# Mosquito2.net
KiCad netlist of a schematic drawn in EAGLE
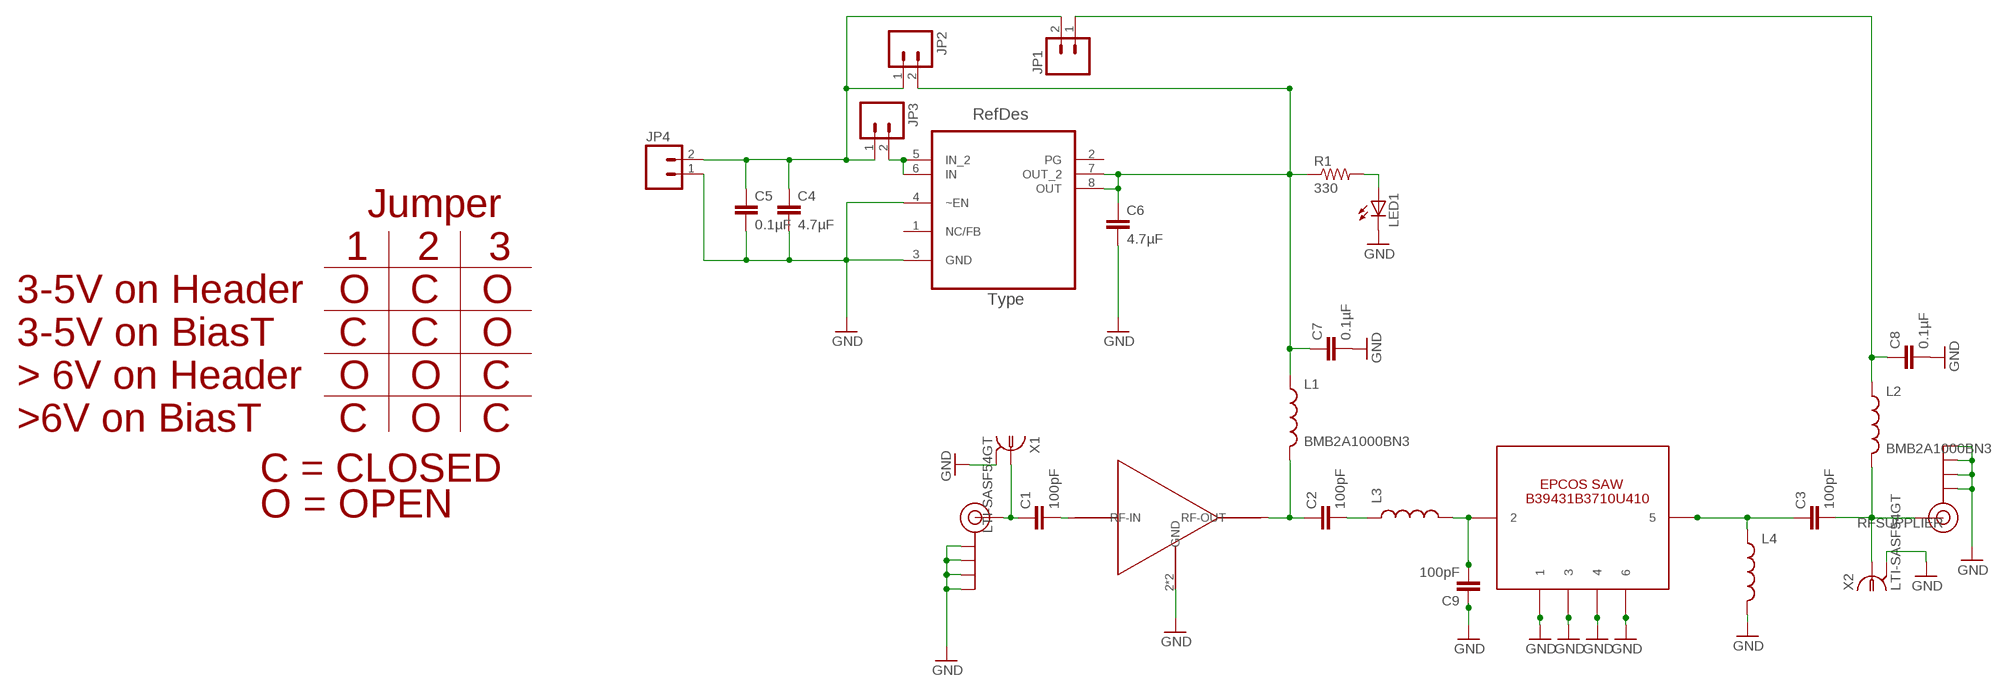
[diagram p0: schematic, sheet 1]

(export (version "E")
  (design (tool "Eeschema 10.0.6"))
  (components
    (comp (ref "C1")
      (value "100pF")
      (footprint "eagle-import:0603-CAP")
      (libsource (lib "eagle-import") (part "CAP0603-CAP"))
    )
    (comp (ref "C2")
      (value "100pF")
      (footprint "eagle-import:0603-CAP")
      (libsource (lib "eagle-import") (part "CAP0603-CAP"))
    )
    (comp (ref "C3")
      (value "100pF")
      (footprint "eagle-import:0603-CAP")
      (libsource (lib "eagle-import") (part "CAP0603-CAP"))
    )
    (comp (ref "C4")
      (value "4.7µF")
      (footprint "eagle-import:0805")
      (libsource (lib "eagle-import") (part "CAP0805"))
    )
    (comp (ref "C5")
      (value "0.1µF")
      (footprint "eagle-import:0603-CAP")
      (libsource (lib "eagle-import") (part "CAP0603-CAP"))
    )
    (comp (ref "C6")
      (value "4.7µF")
      (footprint "eagle-import:0805")
      (libsource (lib "eagle-import") (part "CAP0805"))
    )
    (comp (ref "C7")
      (value "0.1µF")
      (footprint "eagle-import:0603-CAP")
      (libsource (lib "eagle-import") (part "CAP0603-CAP"))
    )
    (comp (ref "C8")
      (value "0.1µF")
      (footprint "eagle-import:0603-CAP")
      (libsource (lib "eagle-import") (part "CAP0603-CAP"))
    )
    (comp (ref "C9")
      (value "100pF")
      (footprint "eagle-import:0603-CAP")
      (libsource (lib "eagle-import") (part "CAP0603-CAP"))
    )
    (comp (ref "IN")
      (value "SMA_EDGE")
      (footprint "eagle-import:SMA-EDGE")
      (libsource (lib "eagle-import") (part "SMA_EDGE"))
    )
    (comp (ref "JP1")
      (value "M02PTH")
      (footprint "eagle-import:1X02")
      (libsource (lib "eagle-import") (part "M02PTH"))
    )
    (comp (ref "JP2")
      (value "M02PTH")
      (footprint "eagle-import:1X02")
      (libsource (lib "eagle-import") (part "M02PTH"))
    )
    (comp (ref "JP3")
      (value "M02PTH")
      (footprint "eagle-import:1X02")
      (libsource (lib "eagle-import") (part "M02PTH"))
    )
    (comp (ref "JP4")
      (value "M02PTH")
      (footprint "eagle-import:1X02")
      (libsource (lib "eagle-import") (part "M02PTH"))
    )
    (comp (ref "L1")
      (value "BMB2A1000BN3")
      (footprint "eagle-import:0805")
      (libsource (lib "eagle-import") (part "INDUCTOR0805"))
    )
    (comp (ref "L2")
      (value "BMB2A1000BN3")
      (footprint "eagle-import:0805")
      (libsource (lib "eagle-import") (part "INDUCTOR0805"))
    )
    (comp (ref "L3")
      (value "INDUCTOR0603")
      (footprint "eagle-import:0603")
      (libsource (lib "eagle-import") (part "SparkFun-Passives_INDUCTOR0603"))
    )
    (comp (ref "L4")
      (value "INDUCTOR0603")
      (footprint "eagle-import:0603")
      (libsource (lib "eagle-import") (part "SparkFun-Passives_INDUCTOR0603"))
    )
    (comp (ref "LED1")
      (value "LEDCHIP-LED0603")
      (footprint "eagle-import:CHIP-LED0603")
      (libsource (lib "eagle-import") (part "LEDCHIP-LED0603"))
    )
    (comp (ref "OUT")
      (value "SMA_EDGE")
      (footprint "eagle-import:SMA-EDGE")
      (libsource (lib "eagle-import") (part "SMA_EDGE"))
    )
    (comp (ref "R1")
      (value "330")
      (footprint "eagle-import:0402-RES")
      (libsource (lib "eagle-import") (part "RESISTOR0402-RES"))
    )
    (comp (ref "U$1")
      (value "AVA_EPCOS_SAW_FILTER")
      (footprint "eagle-import:AVA_EPCOS_SAW_FILTER")
      (libsource (lib "eagle-import") (part "AVA_EPCOS_SAW_FILTER"))
    )
    (comp (ref "U$2")
      (value "PSA4-5043+")
      (footprint "eagle-import:PSA4-5043+")
      (libsource (lib "eagle-import") (part "PSA4-5043+"))
    )
    (comp (ref "U1")
      (value "TPS76633D")
      (footprint "eagle-import:SOIC127P600X175-8N")
      (libsource (lib "eagle-import") (part "TPS76633D"))
    )
    (comp (ref "X1")
      (value "LTI-SASF54GT")
      (footprint "eagle-import:LTI-SASF54GT")
      (libsource (lib "eagle-import") (part "LTI-SASF54GT"))
    )
    (comp (ref "X2")
      (value "LTI-SASF54GT")
      (footprint "eagle-import:LTI-SASF54GT")
      (libsource (lib "eagle-import") (part "LTI-SASF54GT"))
    )
  )
  (nets
    (net (code "1") (name "GND") (class "Default")
      (node (ref "C4") (pin "2") (pinfunction "2_2") (pintype "passive"))
      (node (ref "C5") (pin "2") (pinfunction "2_2") (pintype "passive"))
      (node (ref "C6") (pin "2") (pinfunction "2_2") (pintype "passive"))
      (node (ref "C7") (pin "2") (pinfunction "2_2") (pintype "passive"))
      (node (ref "C8") (pin "2") (pinfunction "2_2") (pintype "passive"))
      (node (ref "C9") (pin "1") (pinfunction "1_1") (pintype "passive"))
      (node (ref "IN") (pin "GND@0") (pinfunction "GND_GND@0") (pintype "bidirectional"))
      (node (ref "IN") (pin "GND@1") (pinfunction "GND_GND@1") (pintype "bidirectional"))
      (node (ref "IN") (pin "GND@2") (pinfunction "GND_GND@2") (pintype "bidirectional"))
      (node (ref "IN") (pin "GND@3") (pinfunction "GND_GND@3") (pintype "bidirectional"))
      (node (ref "JP4") (pin "1") (pinfunction "1_1") (pintype "passive"))
      (node (ref "L4") (pin "2") (pinfunction "2_2") (pintype "passive"))
      (node (ref "LED1") (pin "C") (pinfunction "C_C") (pintype "passive"))
      (node (ref "OUT") (pin "GND@0") (pinfunction "GND_GND@0") (pintype "bidirectional"))
      (node (ref "OUT") (pin "GND@1") (pinfunction "GND_GND@1") (pintype "bidirectional"))
      (node (ref "OUT") (pin "GND@2") (pinfunction "GND_GND@2") (pintype "bidirectional"))
      (node (ref "OUT") (pin "GND@3") (pinfunction "GND_GND@3") (pintype "bidirectional"))
      (node (ref "U$1") (pin "P$1") (pinfunction "1_P$1") (pintype "bidirectional"))
      (node (ref "U$1") (pin "P$3") (pinfunction "3_P$3") (pintype "bidirectional"))
      (node (ref "U$1") (pin "P$4") (pinfunction "4_P$4") (pintype "bidirectional"))
      (node (ref "U$1") (pin "P$6") (pinfunction "6_P$6") (pintype "bidirectional"))
      (node (ref "U$2") (pin "2") (pinfunction "GND_2") (pintype "bidirectional"))
      (node (ref "U$2") (pin "4") (pinfunction "GND_4") (pintype "bidirectional"))
      (node (ref "U1") (pin "3") (pinfunction "GND_3") (pintype "passive"))
      (node (ref "U1") (pin "4") (pinfunction "~{EN}_4") (pintype "input"))
      (node (ref "X1") (pin "2") (pinfunction "2_2") (pintype "passive"))
      (node (ref "X1") (pin "3") (pinfunction "2_3") (pintype "passive"))
      (node (ref "X1") (pin "4") (pinfunction "2_4") (pintype "passive"))
      (node (ref "X1") (pin "5") (pinfunction "2_5") (pintype "passive"))
      (node (ref "X2") (pin "2") (pinfunction "2_2") (pintype "passive"))
      (node (ref "X2") (pin "3") (pinfunction "2_3") (pintype "passive"))
      (node (ref "X2") (pin "4") (pinfunction "2_4") (pintype "passive"))
      (node (ref "X2") (pin "5") (pinfunction "2_5") (pintype "passive"))
    )
    (net (code "2") (name "Net-(C2-Pad2)") (class "Default")
      (node (ref "C2") (pin "2") (pinfunction "2_2") (pintype "passive"))
      (node (ref "L3") (pin "1") (pinfunction "1_1") (pintype "passive"))
    )
    (net (code "3") (name "Net-(C4-Pad1)") (class "Default")
      (node (ref "C4") (pin "1") (pinfunction "1_1") (pintype "passive"))
      (node (ref "C5") (pin "1") (pinfunction "1_1") (pintype "passive"))
      (node (ref "JP1") (pin "2") (pinfunction "2_2") (pintype "passive"))
      (node (ref "JP2") (pin "1") (pinfunction "1_1") (pintype "passive"))
      (node (ref "JP3") (pin "1") (pinfunction "1_1") (pintype "passive"))
      (node (ref "JP4") (pin "2") (pinfunction "2_2") (pintype "passive"))
    )
    (net (code "4") (name "Net-(C8-Pad1)") (class "Default")
      (node (ref "C8") (pin "1") (pinfunction "1_1") (pintype "passive"))
      (node (ref "JP1") (pin "1") (pinfunction "1_1") (pintype "passive"))
      (node (ref "L2") (pin "1") (pinfunction "1_1") (pintype "passive"))
    )
    (net (code "5") (name "Net-(IN-SIGNAL)") (class "Default")
      (node (ref "C1") (pin "1") (pinfunction "1_1") (pintype "passive"))
      (node (ref "IN") (pin "SIG") (pinfunction "SIGNAL_SIG") (pintype "bidirectional"))
      (node (ref "X1") (pin "1") (pinfunction "1_1") (pintype "passive"))
    )
    (net (code "6") (name "Net-(LED1-PadA)") (class "Default")
      (node (ref "LED1") (pin "A") (pinfunction "A_A") (pintype "passive"))
      (node (ref "R1") (pin "2") (pinfunction "2_2") (pintype "passive"))
    )
    (net (code "7") (name "Net-(OUT-SIGNAL)") (class "Default")
      (node (ref "C3") (pin "2") (pinfunction "2_2") (pintype "passive"))
      (node (ref "L2") (pin "2") (pinfunction "2_2") (pintype "passive"))
      (node (ref "OUT") (pin "SIG") (pinfunction "SIGNAL_SIG") (pintype "bidirectional"))
      (node (ref "X2") (pin "1") (pinfunction "1_1") (pintype "passive"))
    )
    (net (code "8") (name "Net-(U$1-2)") (class "Default")
      (node (ref "C9") (pin "2") (pinfunction "2_2") (pintype "passive"))
      (node (ref "L3") (pin "2") (pinfunction "2_2") (pintype "passive"))
      (node (ref "U$1") (pin "P$2") (pinfunction "2_P$2") (pintype "bidirectional"))
    )
    (net (code "9") (name "Net-(U$1-5)") (class "Default")
      (node (ref "C3") (pin "1") (pinfunction "1_1") (pintype "passive"))
      (node (ref "L4") (pin "1") (pinfunction "1_1") (pintype "passive"))
      (node (ref "U$1") (pin "P$5") (pinfunction "5_P$5") (pintype "bidirectional"))
    )
    (net (code "10") (name "Net-(U$2-RF-IN)") (class "Default")
      (node (ref "C1") (pin "2") (pinfunction "2_2") (pintype "passive"))
      (node (ref "U$2") (pin "3") (pinfunction "RF-IN_3") (pintype "bidirectional"))
    )
    (net (code "11") (name "Net-(U$2-RF-OUT)") (class "Default")
      (node (ref "C2") (pin "1") (pinfunction "1_1") (pintype "passive"))
      (node (ref "L1") (pin "2") (pinfunction "2_2") (pintype "passive"))
      (node (ref "U$2") (pin "1") (pinfunction "RF-OUT_1") (pintype "bidirectional"))
    )
    (net (code "12") (name "Net-(U1-IN)") (class "Default")
      (node (ref "JP3") (pin "2") (pinfunction "2_2") (pintype "passive"))
      (node (ref "U1") (pin "5") (pinfunction "IN_2_5") (pintype "input"))
      (node (ref "U1") (pin "6") (pinfunction "IN_6") (pintype "input"))
    )
    (net (code "13") (name "Net-(U1-OUT)") (class "Default")
      (node (ref "C6") (pin "1") (pinfunction "1_1") (pintype "passive"))
      (node (ref "C7") (pin "1") (pinfunction "1_1") (pintype "passive"))
      (node (ref "JP2") (pin "2") (pinfunction "2_2") (pintype "passive"))
      (node (ref "L1") (pin "1") (pinfunction "1_1") (pintype "passive"))
      (node (ref "R1") (pin "1") (pinfunction "1_1") (pintype "passive"))
      (node (ref "U1") (pin "7") (pinfunction "OUT_2_7") (pintype "output"))
      (node (ref "U1") (pin "8") (pinfunction "OUT_8") (pintype "output"))
    )
    (net (code "14") (name "unconnected-(U1-NC{slash}FB-Pad1)") (class "Default")
      (node (ref "U1") (pin "1") (pinfunction "NC/FB_1") (pintype "no_connect"))
    )
    (net (code "15") (name "unconnected-(U1-PG-Pad2)") (class "Default")
      (node (ref "U1") (pin "2") (pinfunction "PG_2") (pintype "output"))
    )
  )
)
